# servo-pyro.net
KiCad netlist of a schematic drawn in EAGLE
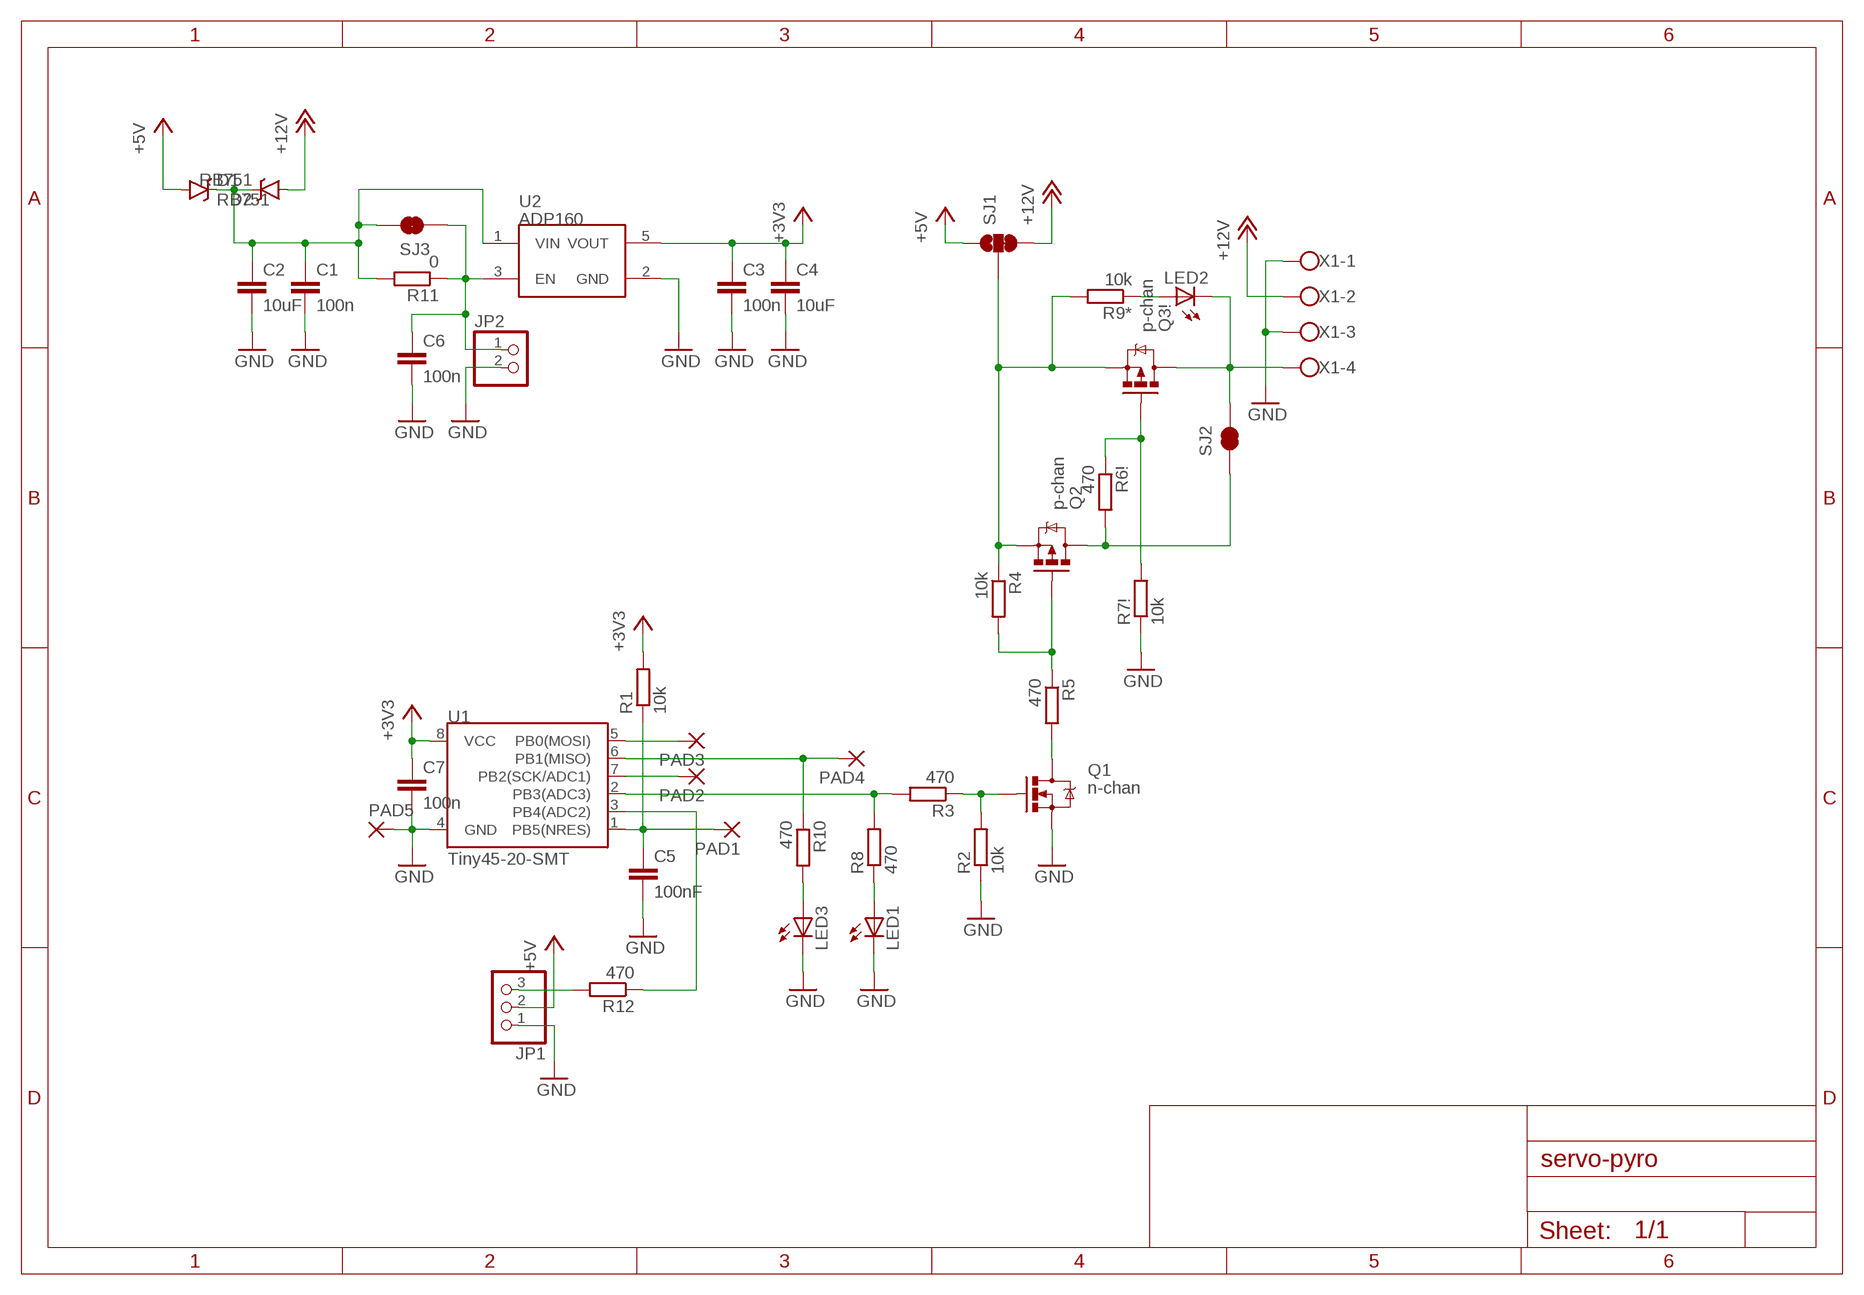
[diagram p0: schematic, sheet 1]

(export (version "E")
  (design (tool "Eeschema 10.0.6"))
  (components
    (comp (ref "C1")
      (value "100n")
      (footprint "eagle-import:C0603K")
      (libsource (lib "eagle-import") (part "C-EUC0603K"))
    )
    (comp (ref "C2")
      (value "10uF")
      (footprint "eagle-import:C0603K")
      (libsource (lib "eagle-import") (part "C-EUC0603K"))
    )
    (comp (ref "C3")
      (value "100n")
      (footprint "eagle-import:C0603K")
      (libsource (lib "eagle-import") (part "C-EUC0603K"))
    )
    (comp (ref "C4")
      (value "10uF")
      (footprint "eagle-import:C0603K")
      (libsource (lib "eagle-import") (part "C-EUC0603K"))
    )
    (comp (ref "C5")
      (value "100nF")
      (footprint "eagle-import:C0603K")
      (libsource (lib "eagle-import") (part "C-EUC0603K"))
    )
    (comp (ref "C6")
      (value "100n")
      (footprint "eagle-import:C0603K")
      (libsource (lib "eagle-import") (part "C-EUC0603K"))
    )
    (comp (ref "C7")
      (value "100n")
      (footprint "eagle-import:C0603K")
      (libsource (lib "eagle-import") (part "C-EUC0603K"))
    )
    (comp (ref "D1")
      (value "RB751")
      (footprint "eagle-import:SOD-523")
      (libsource (lib "eagle-import") (part "DIODE-SCHOTTKY-RB751"))
    )
    (comp (ref "D2")
      (value "RB751")
      (footprint "eagle-import:SOD-523")
      (libsource (lib "eagle-import") (part "DIODE-SCHOTTKY-RB751"))
    )
    (comp (ref "JP1")
      (value "PINHD-1X3")
      (footprint "eagle-import:1X03")
      (libsource (lib "eagle-import") (part "PINHD-1X3"))
    )
    (comp (ref "JP2")
      (value "PINHD-1X2")
      (footprint "eagle-import:1X02")
      (libsource (lib "eagle-import") (part "PINHD-1X2"))
    )
    (comp (ref "LED1")
      (value "LEDCHIPLED_0603")
      (footprint "eagle-import:CHIPLED_0603")
      (libsource (lib "eagle-import") (part "LEDCHIPLED_0603"))
    )
    (comp (ref "LED2")
      (value "LEDCHIPLED_0603")
      (footprint "eagle-import:CHIPLED_0603")
      (libsource (lib "eagle-import") (part "LEDCHIPLED_0603"))
    )
    (comp (ref "LED3")
      (value "LEDCHIPLED_0603")
      (footprint "eagle-import:CHIPLED_0603")
      (libsource (lib "eagle-import") (part "LEDCHIPLED_0603"))
    )
    (comp (ref "PAD1")
      (value "1,6/0,8")
      (footprint "eagle-import:1,6_0,8")
      (libsource (lib "eagle-import") (part "1,6/0,8"))
    )
    (comp (ref "PAD2")
      (value "1,6/0,8")
      (footprint "eagle-import:1,6_0,8")
      (libsource (lib "eagle-import") (part "1,6/0,8"))
    )
    (comp (ref "PAD3")
      (value "1,6/0,8")
      (footprint "eagle-import:1,6_0,8")
      (libsource (lib "eagle-import") (part "1,6/0,8"))
    )
    (comp (ref "PAD4")
      (value "1,6/0,8")
      (footprint "eagle-import:1,6_0,8")
      (libsource (lib "eagle-import") (part "1,6/0,8"))
    )
    (comp (ref "PAD5")
      (value "1,6/0,8")
      (footprint "eagle-import:1,6_0,8")
      (libsource (lib "eagle-import") (part "1,6/0,8"))
    )
    (comp (ref "Q1")
      (value "n-chan")
      (footprint "eagle-import:SOT23-3")
      (libsource (lib "eagle-import") (part "MOSFET-NCHANNELBSS123LT1G"))
    )
    (comp (ref "Q2")
      (value "p-chan")
      (footprint "eagle-import:SOT23-3")
      (libsource (lib "eagle-import") (part "MOSFET-PCHANNELSMD"))
    )
    (comp (ref "Q3!")
      (value "p-chan")
      (footprint "eagle-import:SOT23-3")
      (libsource (lib "eagle-import") (part "MOSFET-PCHANNELSMD"))
    )
    (comp (ref "R1")
      (value "10k")
      (footprint "eagle-import:R0603")
      (libsource (lib "eagle-import") (part "R-EU_R0603"))
    )
    (comp (ref "R2")
      (value "10k")
      (footprint "eagle-import:R0603")
      (libsource (lib "eagle-import") (part "R-EU_R0603"))
    )
    (comp (ref "R3")
      (value "470")
      (footprint "eagle-import:R0603")
      (libsource (lib "eagle-import") (part "R-EU_R0603"))
    )
    (comp (ref "R4")
      (value "10k")
      (footprint "eagle-import:R0603")
      (libsource (lib "eagle-import") (part "R-EU_R0603"))
    )
    (comp (ref "R5")
      (value "470")
      (footprint "eagle-import:R0603")
      (libsource (lib "eagle-import") (part "R-EU_R0603"))
    )
    (comp (ref "R6!")
      (value "470")
      (footprint "eagle-import:R0603")
      (libsource (lib "eagle-import") (part "R-EU_R0603"))
    )
    (comp (ref "R7!")
      (value "10k")
      (footprint "eagle-import:R0603")
      (libsource (lib "eagle-import") (part "R-EU_R0603"))
    )
    (comp (ref "R8")
      (value "470")
      (footprint "eagle-import:R0603")
      (libsource (lib "eagle-import") (part "R-EU_R0603"))
    )
    (comp (ref "R9*")
      (value "10k")
      (footprint "eagle-import:R0603")
      (libsource (lib "eagle-import") (part "R-EU_R0603"))
    )
    (comp (ref "R10")
      (value "470")
      (footprint "eagle-import:R0603")
      (libsource (lib "eagle-import") (part "R-EU_R0603"))
    )
    (comp (ref "R11")
      (value "0")
      (footprint "eagle-import:R0603")
      (libsource (lib "eagle-import") (part "R-EU_R0603"))
    )
    (comp (ref "R12")
      (value "470")
      (footprint "eagle-import:R0603")
      (libsource (lib "eagle-import") (part "R-EU_R0603"))
    )
    (comp (ref "SJ1")
      (value "JUMPER-PAD-3-2OF3_NC_BY_TRACE_LARGE")
      (footprint "eagle-import:PAD-JUMPER-3-2OF3_NC_BY_TRACE_YES_SILK_LARGE")
      (libsource (lib "eagle-import") (part "JUMPER-PAD-3-2OF3_NC_BY_TRACE_LARGE"))
    )
    (comp (ref "SJ2")
      (value "JUMPER-PAD-2-NC_BY_TRACENO_SILK")
      (footprint "eagle-import:PAD-JUMPER-2-NC_BY_TRACE_NO_SILK")
      (libsource (lib "eagle-import") (part "JUMPER-PAD-2-NC_BY_TRACENO_SILK"))
    )
    (comp (ref "SJ3")
      (value "JUMPER-PAD-2-NC_BY_TRACENO_SILK")
      (footprint "eagle-import:PAD-JUMPER-2-NC_BY_TRACE_NO_SILK")
      (libsource (lib "eagle-import") (part "JUMPER-PAD-2-NC_BY_TRACENO_SILK"))
    )
    (comp (ref "U1")
      (value "Tiny45-20-SMT")
      (footprint "eagle-import:SO08-EIAJ")
      (libsource (lib "eagle-import") (part "ATTINY45TINY45-20-SMT"))
    )
    (comp (ref "U2")
      (value "ADP160")
      (footprint "eagle-import:SOT23-5")
      (libsource (lib "eagle-import") (part "ADP160"))
    )
    (comp (ref "X1")
      (value "W237-4")
      (footprint "eagle-import:W237-4")
      (libsource (lib "eagle-import") (part "W237-4"))
    )
  )
  (nets
    (net (code "1") (name "+3V3") (class "Default")
      (node (ref "C3") (pin "1") (pinfunction "1_1") (pintype "passive"))
      (node (ref "C4") (pin "1") (pinfunction "1_1") (pintype "passive"))
      (node (ref "C7") (pin "1") (pinfunction "1_1") (pintype "passive"))
      (node (ref "R1") (pin "2") (pinfunction "2_2") (pintype "passive"))
      (node (ref "U1") (pin "8") (pinfunction "VCC_8") (pintype "bidirectional"))
      (node (ref "U2") (pin "5") (pinfunction "VOUT_5") (pintype "bidirectional"))
    )
    (net (code "2") (name "+5V") (class "Default")
      (node (ref "D1") (pin "A") (pinfunction "A_A") (pintype "passive"))
      (node (ref "JP1") (pin "2") (pinfunction "2_2") (pintype "passive"))
      (node (ref "SJ1") (pin "1") (pinfunction "1_1") (pintype "passive"))
    )
    (net (code "3") (name "+12V") (class "Default")
      (node (ref "D2") (pin "A") (pinfunction "A_A") (pintype "passive"))
      (node (ref "SJ1") (pin "3") (pinfunction "3_3") (pintype "passive"))
      (node (ref "X1") (pin "2") (pinfunction "KL_2") (pintype "passive"))
    )
    (net (code "4") (name "GND") (class "Default")
      (node (ref "C1") (pin "2") (pinfunction "2_2") (pintype "passive"))
      (node (ref "C2") (pin "2") (pinfunction "2_2") (pintype "passive"))
      (node (ref "C3") (pin "2") (pinfunction "2_2") (pintype "passive"))
      (node (ref "C4") (pin "2") (pinfunction "2_2") (pintype "passive"))
      (node (ref "C5") (pin "2") (pinfunction "2_2") (pintype "passive"))
      (node (ref "C6") (pin "2") (pinfunction "2_2") (pintype "passive"))
      (node (ref "C7") (pin "2") (pinfunction "2_2") (pintype "passive"))
      (node (ref "JP1") (pin "1") (pinfunction "1_1") (pintype "passive"))
      (node (ref "JP2") (pin "2") (pinfunction "2_2") (pintype "passive"))
      (node (ref "LED1") (pin "C") (pinfunction "C_C") (pintype "passive"))
      (node (ref "LED3") (pin "C") (pinfunction "C_C") (pintype "passive"))
      (node (ref "PAD5") (pin "1") (pinfunction "P_1") (pintype "passive"))
      (node (ref "Q1") (pin "2") (pinfunction "S_2") (pintype "passive"))
      (node (ref "R2") (pin "1") (pinfunction "1_1") (pintype "passive"))
      (node (ref "R7!") (pin "1") (pinfunction "1_1") (pintype "passive"))
      (node (ref "U1") (pin "4") (pinfunction "GND_4") (pintype "bidirectional"))
      (node (ref "U2") (pin "2") (pinfunction "GND_2") (pintype "bidirectional"))
      (node (ref "X1") (pin "1") (pinfunction "KL_1") (pintype "passive"))
      (node (ref "X1") (pin "3") (pinfunction "KL_3") (pintype "passive"))
    )
    (net (code "5") (name "Net-(JP1-Pad3)") (class "Default")
      (node (ref "JP1") (pin "3") (pinfunction "3_3") (pintype "passive"))
      (node (ref "R12") (pin "2") (pinfunction "2_2") (pintype "passive"))
    )
    (net (code "6") (name "Net-(LED1-PadA)") (class "Default")
      (node (ref "LED1") (pin "A") (pinfunction "A_A") (pintype "passive"))
      (node (ref "R8") (pin "1") (pinfunction "1_1") (pintype "passive"))
    )
    (net (code "7") (name "Net-(LED2-PadA)") (class "Default")
      (node (ref "LED2") (pin "A") (pinfunction "A_A") (pintype "passive"))
      (node (ref "R9*") (pin "1") (pinfunction "1_1") (pintype "passive"))
    )
    (net (code "8") (name "Net-(LED3-PadA)") (class "Default")
      (node (ref "LED3") (pin "A") (pinfunction "A_A") (pintype "passive"))
      (node (ref "R10") (pin "2") (pinfunction "2_2") (pintype "passive"))
    )
    (net (code "9") (name "Net-(PAD1-P)") (class "Default")
      (node (ref "C5") (pin "1") (pinfunction "1_1") (pintype "passive"))
      (node (ref "PAD1") (pin "1") (pinfunction "P_1") (pintype "passive"))
      (node (ref "R1") (pin "1") (pinfunction "1_1") (pintype "passive"))
      (node (ref "U1") (pin "1") (pinfunction "PB5(NRES)_1") (pintype "bidirectional"))
    )
    (net (code "10") (name "Net-(PAD2-P)") (class "Default")
      (node (ref "PAD2") (pin "1") (pinfunction "P_1") (pintype "passive"))
      (node (ref "U1") (pin "7") (pinfunction "PB2(SCK/ADC1)_7") (pintype "bidirectional"))
    )
    (net (code "11") (name "Net-(PAD3-P)") (class "Default")
      (node (ref "PAD3") (pin "1") (pinfunction "P_1") (pintype "passive"))
      (node (ref "U1") (pin "5") (pinfunction "PB0(MOSI)_5") (pintype "bidirectional"))
    )
    (net (code "12") (name "Net-(PAD4-P)") (class "Default")
      (node (ref "PAD4") (pin "1") (pinfunction "P_1") (pintype "passive"))
      (node (ref "R10") (pin "1") (pinfunction "1_1") (pintype "passive"))
      (node (ref "U1") (pin "6") (pinfunction "PB1(MISO)_6") (pintype "bidirectional"))
    )
    (net (code "13") (name "Net-(Q1-D)") (class "Default")
      (node (ref "Q1") (pin "3") (pinfunction "D_3") (pintype "passive"))
      (node (ref "R5") (pin "2") (pinfunction "2_2") (pintype "passive"))
    )
    (net (code "14") (name "Net-(Q1-G)") (class "Default")
      (node (ref "Q1") (pin "1") (pinfunction "G_1") (pintype "passive"))
      (node (ref "R2") (pin "2") (pinfunction "2_2") (pintype "passive"))
      (node (ref "R3") (pin "1") (pinfunction "1_1") (pintype "passive"))
    )
    (net (code "15") (name "Net-(Q2-D)") (class "Default")
      (node (ref "Q2") (pin "3") (pinfunction "D_3") (pintype "passive"))
      (node (ref "R6!") (pin "2") (pinfunction "2_2") (pintype "passive"))
      (node (ref "SJ2") (pin "1") (pinfunction "1_1") (pintype "passive"))
    )
    (net (code "16") (name "Net-(Q2-G)") (class "Default")
      (node (ref "Q2") (pin "1") (pinfunction "G_1") (pintype "passive"))
      (node (ref "R4") (pin "2") (pinfunction "2_2") (pintype "passive"))
      (node (ref "R5") (pin "1") (pinfunction "1_1") (pintype "passive"))
    )
    (net (code "17") (name "Net-(Q2-S)") (class "Default")
      (node (ref "Q2") (pin "2") (pinfunction "S_2") (pintype "passive"))
      (node (ref "Q3!") (pin "2") (pinfunction "S_2") (pintype "passive"))
      (node (ref "R4") (pin "1") (pinfunction "1_1") (pintype "passive"))
      (node (ref "R9*") (pin "2") (pinfunction "2_2") (pintype "passive"))
      (node (ref "SJ1") (pin "2") (pinfunction "2_2") (pintype "passive"))
    )
    (net (code "18") (name "Net-(Q3!-D)") (class "Default")
      (node (ref "LED2") (pin "C") (pinfunction "C_C") (pintype "passive"))
      (node (ref "Q3!") (pin "3") (pinfunction "D_3") (pintype "passive"))
      (node (ref "SJ2") (pin "2") (pinfunction "2_2") (pintype "passive"))
      (node (ref "X1") (pin "4") (pinfunction "KL_4") (pintype "passive"))
    )
    (net (code "19") (name "Net-(Q3!-G)") (class "Default")
      (node (ref "Q3!") (pin "1") (pinfunction "G_1") (pintype "passive"))
      (node (ref "R6!") (pin "1") (pinfunction "1_1") (pintype "passive"))
      (node (ref "R7!") (pin "2") (pinfunction "2_2") (pintype "passive"))
    )
    (net (code "20") (name "Net-(U1-PB3(ADC3))") (class "Default")
      (node (ref "R3") (pin "2") (pinfunction "2_2") (pintype "passive"))
      (node (ref "R8") (pin "2") (pinfunction "2_2") (pintype "passive"))
      (node (ref "U1") (pin "2") (pinfunction "PB3(ADC3)_2") (pintype "bidirectional"))
    )
    (net (code "21") (name "Net-(U1-PB4(ADC2))") (class "Default")
      (node (ref "R12") (pin "1") (pinfunction "1_1") (pintype "passive"))
      (node (ref "U1") (pin "3") (pinfunction "PB4(ADC2)_3") (pintype "bidirectional"))
    )
    (net (code "22") (name "Net-(U2-EN)") (class "Default")
      (node (ref "C6") (pin "1") (pinfunction "1_1") (pintype "passive"))
      (node (ref "JP2") (pin "1") (pinfunction "1_1") (pintype "passive"))
      (node (ref "R11") (pin "1") (pinfunction "1_1") (pintype "passive"))
      (node (ref "SJ3") (pin "1") (pinfunction "1_1") (pintype "passive"))
      (node (ref "U2") (pin "3") (pinfunction "EN_3") (pintype "bidirectional"))
    )
    (net (code "23") (name "Net-(U2-VIN)") (class "Default")
      (node (ref "C1") (pin "1") (pinfunction "1_1") (pintype "passive"))
      (node (ref "C2") (pin "1") (pinfunction "1_1") (pintype "passive"))
      (node (ref "D1") (pin "C") (pinfunction "C_C") (pintype "passive"))
      (node (ref "D2") (pin "C") (pinfunction "C_C") (pintype "passive"))
      (node (ref "R11") (pin "2") (pinfunction "2_2") (pintype "passive"))
      (node (ref "SJ3") (pin "2") (pinfunction "2_2") (pintype "passive"))
      (node (ref "U2") (pin "1") (pinfunction "VIN_1") (pintype "bidirectional"))
    )
  )
)
